# Hello.net
KiCad netlist of a schematic drawn in EAGLE
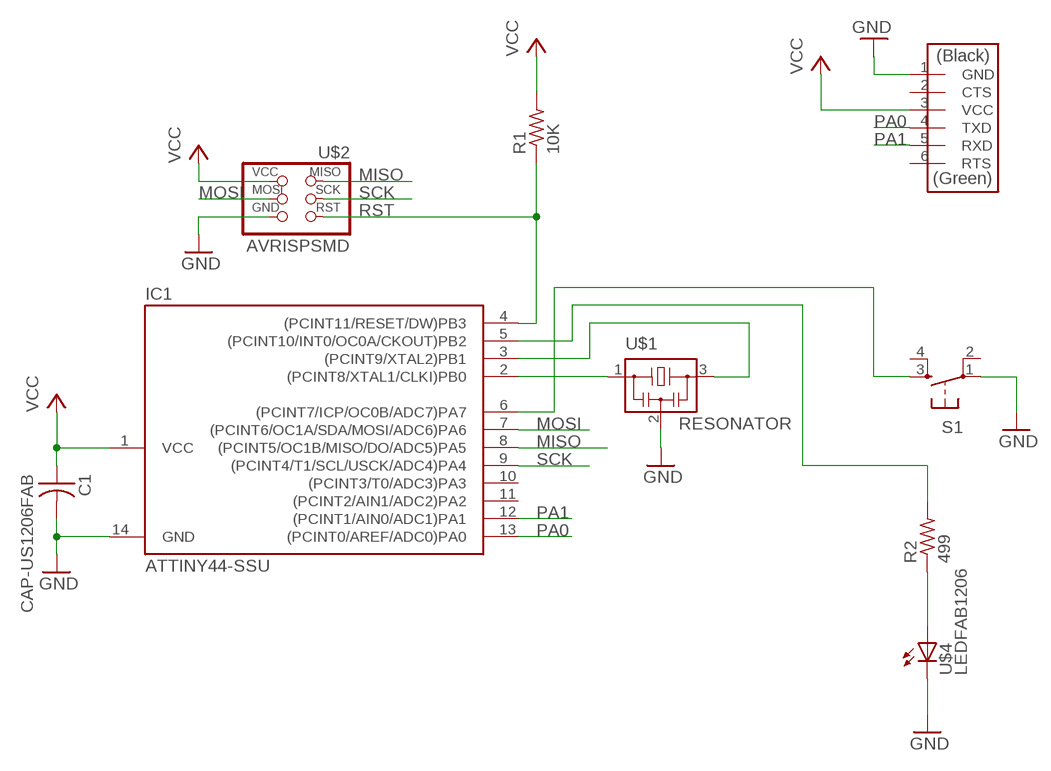
[diagram p0: schematic, sheet 1]

(export (version "E")
  (design (tool "Eeschema 10.0.6"))
  (components
    (comp (ref "C1")
      (value "CAP-US1206FAB")
      (footprint "eagle-import:C1206FAB")
      (libsource (lib "eagle-import") (part "CAP-US1206FAB"))
    )
    (comp (ref "IC1")
      (value "ATTINY44-SSU")
      (footprint "eagle-import:SOIC14")
      (libsource (lib "eagle-import") (part "ATTINY44-SSU"))
    )
    (comp (ref "R1")
      (value "10K")
      (footprint "eagle-import:R1206FAB")
      (libsource (lib "eagle-import") (part "RES-US1206FAB"))
    )
    (comp (ref "R2")
      (value "499")
      (footprint "eagle-import:R1206FAB")
      (libsource (lib "eagle-import") (part "RES-US1206FAB"))
    )
    (comp (ref "S1")
      (value "6MM_SWITCH6MM_SWITCH")
      (footprint "eagle-import:6MM_SWITCH")
      (libsource (lib "eagle-import") (part "6MM_SWITCH6MM_SWITCH"))
    )
    (comp (ref "U$1")
      (value "RESONATOR")
      (footprint "eagle-import:EFOBM")
      (libsource (lib "eagle-import") (part "RESONATOR"))
    )
    (comp (ref "U$2")
      (value "AVRISPSMD")
      (footprint "eagle-import:2X03SMD")
      (libsource (lib "eagle-import") (part "AVRISPSMD"))
    )
    (comp (ref "U$3")
      (value "FTDI-SMD-HEADER")
      (footprint "eagle-import:1X06SMD")
      (libsource (lib "eagle-import") (part "FTDI-SMD-HEADER"))
    )
    (comp (ref "U$4")
      (value "LEDFAB1206")
      (footprint "eagle-import:LED1206FAB")
      (libsource (lib "eagle-import") (part "LEDFAB1206"))
    )
  )
  (nets
    (net (code "1") (name "/MISO") (class "Default")
      (node (ref "IC1") (pin "8") (pinfunction "(PCINT5/OC1B/MISO/DO/ADC5)PA5_8") (pintype "bidirectional"))
      (node (ref "U$2") (pin "1") (pinfunction "MISO_1") (pintype "passive"))
    )
    (net (code "2") (name "/MOSI") (class "Default")
      (node (ref "IC1") (pin "7") (pinfunction "(PCINT6/OC1A/SDA/MOSI/ADC6)PA6_7") (pintype "bidirectional"))
      (node (ref "U$2") (pin "4") (pinfunction "MOSI_4") (pintype "passive"))
    )
    (net (code "3") (name "/PA0") (class "Default")
      (node (ref "IC1") (pin "13") (pinfunction "(PCINT0/AREF/ADC0)PA0_13") (pintype "bidirectional"))
      (node (ref "U$3") (pin "4") (pinfunction "TXD_4") (pintype "bidirectional"))
    )
    (net (code "4") (name "/PA1") (class "Default")
      (node (ref "IC1") (pin "12") (pinfunction "(PCINT1/AIN0/ADC1)PA1_12") (pintype "bidirectional"))
      (node (ref "U$3") (pin "5") (pinfunction "RXD_5") (pintype "bidirectional"))
    )
    (net (code "5") (name "/RST") (class "Default")
      (node (ref "IC1") (pin "4") (pinfunction "(PCINT11/RESET/DW)PB3_4") (pintype "bidirectional"))
      (node (ref "R1") (pin "1") (pinfunction "1_1") (pintype "passive"))
      (node (ref "U$2") (pin "5") (pinfunction "RST_5") (pintype "passive"))
    )
    (net (code "6") (name "/SCK") (class "Default")
      (node (ref "IC1") (pin "9") (pinfunction "(PCINT4/T1/SCL/USCK/ADC4)PA4_9") (pintype "bidirectional"))
      (node (ref "U$2") (pin "3") (pinfunction "SCK_3") (pintype "passive"))
    )
    (net (code "7") (name "GND") (class "Default")
      (node (ref "C1") (pin "2") (pinfunction "2_2") (pintype "passive"))
      (node (ref "IC1") (pin "14") (pinfunction "GND_14") (pintype "power_in"))
      (node (ref "S1") (pin "1") (pinfunction "P_1") (pintype "passive"))
      (node (ref "U$1") (pin "2") (pinfunction "2_2") (pintype "passive"))
      (node (ref "U$2") (pin "6") (pinfunction "GND_6") (pintype "passive"))
      (node (ref "U$3") (pin "1") (pinfunction "GND_1") (pintype "bidirectional"))
      (node (ref "U$4") (pin "2") (pinfunction "C_2") (pintype "passive"))
    )
    (net (code "8") (name "Net-(IC1-(PCINT7{slash}ICP{slash}OC0B{slash}ADC7)PA7)") (class "Default")
      (node (ref "IC1") (pin "6") (pinfunction "(PCINT7/ICP/OC0B/ADC7)PA7_6") (pintype "bidirectional"))
      (node (ref "S1") (pin "3") (pinfunction "S_3") (pintype "passive"))
    )
    (net (code "9") (name "Net-(IC1-(PCINT8{slash}XTAL1{slash}CLKI)PB0)") (class "Default")
      (node (ref "IC1") (pin "2") (pinfunction "(PCINT8/XTAL1/CLKI)PB0_2") (pintype "bidirectional"))
      (node (ref "U$1") (pin "1") (pinfunction "1_1") (pintype "passive"))
    )
    (net (code "10") (name "Net-(IC1-(PCINT9{slash}XTAL2)PB1)") (class "Default")
      (node (ref "IC1") (pin "3") (pinfunction "(PCINT9/XTAL2)PB1_3") (pintype "bidirectional"))
      (node (ref "U$1") (pin "3") (pinfunction "3_3") (pintype "passive"))
    )
    (net (code "11") (name "Net-(IC1-(PCINT10{slash}INT0{slash}OC0A{slash}CKOUT)PB2)") (class "Default")
      (node (ref "IC1") (pin "5") (pinfunction "(PCINT10/INT0/OC0A/CKOUT)PB2_5") (pintype "bidirectional"))
      (node (ref "R2") (pin "2") (pinfunction "2_2") (pintype "passive"))
    )
    (net (code "12") (name "Net-(U$4-A)") (class "Default")
      (node (ref "R2") (pin "1") (pinfunction "1_1") (pintype "passive"))
      (node (ref "U$4") (pin "1") (pinfunction "A_1") (pintype "passive"))
    )
    (net (code "13") (name "VCC") (class "Default")
      (node (ref "C1") (pin "1") (pinfunction "1_1") (pintype "passive"))
      (node (ref "IC1") (pin "1") (pinfunction "VCC_1") (pintype "power_in"))
      (node (ref "R1") (pin "2") (pinfunction "2_2") (pintype "passive"))
      (node (ref "U$2") (pin "2") (pinfunction "VCC_2") (pintype "passive"))
      (node (ref "U$3") (pin "3") (pinfunction "VCC_3") (pintype "bidirectional"))
    )
    (net (code "14") (name "unconnected-(IC1-(PCINT2{slash}AIN1{slash}ADC2)PA2-Pad11)") (class "Default")
      (node (ref "IC1") (pin "11") (pinfunction "(PCINT2/AIN1/ADC2)PA2_11") (pintype "bidirectional"))
    )
    (net (code "15") (name "unconnected-(IC1-(PCINT3{slash}T0{slash}ADC3)PA3-Pad10)") (class "Default")
      (node (ref "IC1") (pin "10") (pinfunction "(PCINT3/T0/ADC3)PA3_10") (pintype "bidirectional"))
    )
    (net (code "16") (name "unconnected-(S1-P1-Pad2)") (class "Default")
      (node (ref "S1") (pin "2") (pinfunction "P1_2") (pintype "passive"))
    )
    (net (code "17") (name "unconnected-(S1-S1-Pad4)") (class "Default")
      (node (ref "S1") (pin "4") (pinfunction "S1_4") (pintype "passive"))
    )
    (net (code "18") (name "unconnected-(U$3-CTS-Pad2)") (class "Default")
      (node (ref "U$3") (pin "2") (pinfunction "CTS_2") (pintype "bidirectional"))
    )
    (net (code "19") (name "unconnected-(U$3-RTS-Pad6)") (class "Default")
      (node (ref "U$3") (pin "6") (pinfunction "RTS_6") (pintype "bidirectional"))
    )
  )
)
